# ESP32.net
KiCad netlist of a schematic drawn in Altium Designer
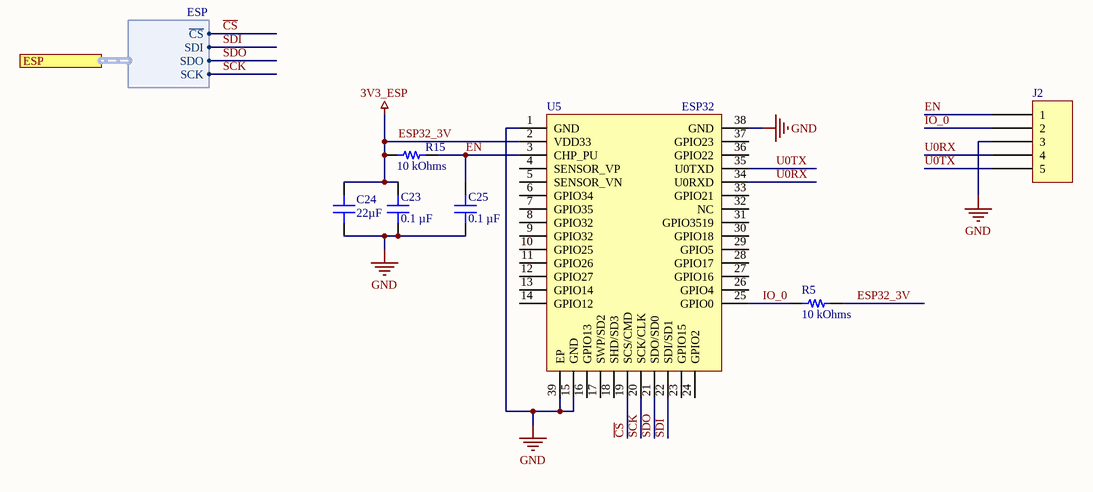
[diagram p0: ESP32.SchDoc]

(export (version "E")
  (design (tool "Eeschema 10.0.6"))
  (components
    (comp (ref "C23")
      (value "0.1 µF")
      (footprint "CAP 0402_1005")
      (description "CAP CER 0.1UF 25V X5R 0402")
      (fields
        (field (name "PART NUMBER") "C1005X5R1E104K050BC")
        (field (name "MANUFACTURER") "TDK Corporation")
      )
      (libsource (lib "Celestial Altium Library - altium_library") (part "Capacitor"))
    )
    (comp (ref "C24")
      (value "22µF")
      (footprint "CAP 0805_2012")
      (description "CAP CER 22UF 16V X5R 0805")
      (fields
        (field (name "PART NUMBER") "CL21A226MOQNNNE")
        (field (name "MANUFACTURER") "Samsung Electro-Mechanics")
      )
      (libsource (lib "Celestial Altium Library - altium_library") (part "Capacitor"))
    )
    (comp (ref "C25")
      (value "0.1 µF")
      (footprint "CAP 0402_1005")
      (description "CAP CER 0.1UF 25V X5R 0402")
      (fields
        (field (name "PART NUMBER") "C1005X5R1E104K050BC")
        (field (name "MANUFACTURER") "TDK Corporation")
      )
      (libsource (lib "Celestial Altium Library - altium_library") (part "Capacitor"))
    )
    (comp (ref "J2")
      (value "SM05B-SRSS-TB(LF)(SN)")
      (footprint "JST SM05B-SRSS-TB")
      (description "CONN HEADER SMD R/A 5POS 1MM")
      (fields (field (name "MANUFACTURER") "JST Sales America Inc."))
      (libsource (lib "Celestial Altium Library - altium_library") (part "5 Pin"))
    )
    (comp (ref "R5")
      (value "10 kOhms")
      (footprint "RES 0402_1005")
      (description "RES SMD 10K OHM 0.5% 1/16W 0402")
      (fields (field (name "PART NUMBER") "CRCW040210K0DHEDP") (field (name "MANUFACTURER") "Vishay Dale"))
      (libsource (lib "Celestial Altium Library - altium_library") (part "Resistor"))
    )
    (comp (ref "R15")
      (value "10 kOhms")
      (footprint "RES 0402_1005")
      (description "RES SMD 10K OHM 0.5% 1/16W 0402")
      (fields (field (name "PART NUMBER") "CRCW040210K0DHEDP") (field (name "MANUFACTURER") "Vishay Dale"))
      (libsource (lib "Celestial Altium Library - altium_library") (part "Resistor"))
    )
    (comp (ref "U5")
      (value "ESP32")
      (footprint "Espressif ESP32-WROOM-32")
      (libsource (lib "IC") (part "ESP32"))
    )
  )
  (nets
    (net (code "2") (name "/EN") (class "Default")
      (node (ref "C25") (pin "2") (pinfunction "2_2") (pintype "passive"))
      (node (ref "J2") (pin "1") (pinfunction "1_1") (pintype "passive"))
      (node (ref "R15") (pin "2") (pinfunction "2_2") (pintype "passive"))
      (node (ref "U5") (pin "3") (pinfunction "CHP_PU_3") (pintype "passive"))
    )
    (net (code "3") (name "/IO_0") (class "Default")
      (node (ref "J2") (pin "2") (pinfunction "2_2") (pintype "passive"))
      (node (ref "R5") (pin "1") (pinfunction "1_1") (pintype "passive"))
      (node (ref "U5") (pin "25") (pinfunction "GPIO0_25") (pintype "passive"))
    )
    (net (code "4") (name "/SCK") (class "Default")
      (node (ref "U5") (pin "20") (pinfunction "SCK/CLK_20") (pintype "passive"))
    )
    (net (code "5") (name "/SDI") (class "Default")
      (node (ref "U5") (pin "22") (pinfunction "SDI/SD1_22") (pintype "passive"))
    )
    (net (code "6") (name "/SDO") (class "Default")
      (node (ref "U5") (pin "21") (pinfunction "SDO/SD0_21") (pintype "passive"))
    )
    (net (code "7") (name "/U0RX") (class "Default")
      (node (ref "J2") (pin "4") (pinfunction "4_4") (pintype "passive"))
      (node (ref "U5") (pin "34") (pinfunction "U0RXD_34") (pintype "passive"))
    )
    (net (code "8") (name "/U0TX") (class "Default")
      (node (ref "J2") (pin "5") (pinfunction "5_5") (pintype "passive"))
      (node (ref "U5") (pin "35") (pinfunction "U0TXD_35") (pintype "passive"))
    )
    (net (code "10") (name "/~{CS}") (class "Default")
      (node (ref "U5") (pin "19") (pinfunction "SCS/CMD_19") (pintype "passive"))
    )
    (net (code "11") (name "3V3_ESP") (class "Default")
      (node (ref "C23") (pin "2") (pinfunction "2_2") (pintype "passive"))
      (node (ref "C24") (pin "2") (pinfunction "2_2") (pintype "passive"))
      (node (ref "R15") (pin "1") (pinfunction "1_1") (pintype "passive"))
      (node (ref "R5") (pin "2") (pinfunction "2_2") (pintype "passive"))
      (node (ref "U5") (pin "2") (pinfunction "VDD33_2") (pintype "passive"))
    )
    (net (code "12") (name "GND") (class "Default")
      (node (ref "C23") (pin "1") (pinfunction "1_1") (pintype "passive"))
      (node (ref "C24") (pin "1") (pinfunction "1_1") (pintype "passive"))
      (node (ref "C25") (pin "1") (pinfunction "1_1") (pintype "passive"))
      (node (ref "J2") (pin "3") (pinfunction "3_3") (pintype "passive"))
      (node (ref "U5") (pin "1") (pinfunction "GND_1") (pintype "passive"))
      (node (ref "U5") (pin "15") (pinfunction "GND_15") (pintype "passive"))
      (node (ref "U5") (pin "38") (pinfunction "GND_38") (pintype "passive"))
      (node (ref "U5") (pin "39") (pinfunction "EP_39") (pintype "passive"))
    )
    (net (code "13") (name "unconnected-(U5-GPIO2-Pad24)") (class "Default")
      (node (ref "U5") (pin "24") (pinfunction "GPIO2_24") (pintype "passive"))
    )
    (net (code "14") (name "unconnected-(U5-GPIO4-Pad26)") (class "Default")
      (node (ref "U5") (pin "26") (pinfunction "GPIO4_26") (pintype "passive"))
    )
    (net (code "15") (name "unconnected-(U5-GPIO5-Pad29)") (class "Default")
      (node (ref "U5") (pin "29") (pinfunction "GPIO5_29") (pintype "passive"))
    )
    (net (code "16") (name "unconnected-(U5-GPIO12-Pad14)") (class "Default")
      (node (ref "U5") (pin "14") (pinfunction "GPIO12_14") (pintype "passive"))
    )
    (net (code "17") (name "unconnected-(U5-GPIO13-Pad16)") (class "Default")
      (node (ref "U5") (pin "16") (pinfunction "GPIO13_16") (pintype "passive"))
    )
    (net (code "18") (name "unconnected-(U5-GPIO14-Pad13)") (class "Default")
      (node (ref "U5") (pin "13") (pinfunction "GPIO14_13") (pintype "passive"))
    )
    (net (code "19") (name "unconnected-(U5-GPIO15-Pad23)") (class "Default")
      (node (ref "U5") (pin "23") (pinfunction "GPIO15_23") (pintype "passive"))
    )
    (net (code "20") (name "unconnected-(U5-GPIO16-Pad27)") (class "Default")
      (node (ref "U5") (pin "27") (pinfunction "GPIO16_27") (pintype "passive"))
    )
    (net (code "21") (name "unconnected-(U5-GPIO17-Pad28)") (class "Default")
      (node (ref "U5") (pin "28") (pinfunction "GPIO17_28") (pintype "passive"))
    )
    (net (code "22") (name "unconnected-(U5-GPIO18-Pad30)") (class "Default")
      (node (ref "U5") (pin "30") (pinfunction "GPIO18_30") (pintype "passive"))
    )
    (net (code "23") (name "unconnected-(U5-GPIO21-Pad33)") (class "Default")
      (node (ref "U5") (pin "33") (pinfunction "GPIO21_33") (pintype "passive"))
    )
    (net (code "24") (name "unconnected-(U5-GPIO22-Pad36)") (class "Default")
      (node (ref "U5") (pin "36") (pinfunction "GPIO22_36") (pintype "passive"))
    )
    (net (code "25") (name "unconnected-(U5-GPIO23-Pad37)") (class "Default")
      (node (ref "U5") (pin "37") (pinfunction "GPIO23_37") (pintype "passive"))
    )
    (net (code "26") (name "unconnected-(U5-GPIO25-Pad10)") (class "Default")
      (node (ref "U5") (pin "10") (pinfunction "GPIO25_10") (pintype "passive"))
    )
    (net (code "27") (name "unconnected-(U5-GPIO26-Pad11)") (class "Default")
      (node (ref "U5") (pin "11") (pinfunction "GPIO26_11") (pintype "passive"))
    )
    (net (code "28") (name "unconnected-(U5-GPIO27-Pad12)") (class "Default")
      (node (ref "U5") (pin "12") (pinfunction "GPIO27_12") (pintype "passive"))
    )
    (net (code "29") (name "unconnected-(U5-GPIO32-Pad8)") (class "Default")
      (node (ref "U5") (pin "8") (pinfunction "GPIO32_8") (pintype "passive"))
    )
    (net (code "30") (name "unconnected-(U5-GPIO32-Pad9)") (class "Default")
      (node (ref "U5") (pin "9") (pinfunction "GPIO32_9") (pintype "passive"))
    )
    (net (code "31") (name "unconnected-(U5-GPIO34-Pad6)") (class "Default")
      (node (ref "U5") (pin "6") (pinfunction "GPIO34_6") (pintype "passive"))
    )
    (net (code "32") (name "unconnected-(U5-GPIO35-Pad7)") (class "Default")
      (node (ref "U5") (pin "7") (pinfunction "GPIO35_7") (pintype "passive"))
    )
    (net (code "33") (name "unconnected-(U5-GPIO3519-Pad31)") (class "Default")
      (node (ref "U5") (pin "31") (pinfunction "GPIO3519_31") (pintype "passive"))
    )
    (net (code "34") (name "unconnected-(U5-NC-Pad32)") (class "Default")
      (node (ref "U5") (pin "32") (pinfunction "NC_32") (pintype "passive"))
    )
    (net (code "35") (name "unconnected-(U5-SENSOR_VN-Pad5)") (class "Default")
      (node (ref "U5") (pin "5") (pinfunction "SENSOR_VN_5") (pintype "passive"))
    )
    (net (code "36") (name "unconnected-(U5-SENSOR_VP-Pad4)") (class "Default")
      (node (ref "U5") (pin "4") (pinfunction "SENSOR_VP_4") (pintype "passive"))
    )
    (net (code "37") (name "unconnected-(U5-SHD{slash}SD3-Pad18)") (class "Default")
      (node (ref "U5") (pin "18") (pinfunction "SHD/SD3_18") (pintype "passive"))
    )
    (net (code "38") (name "unconnected-(U5-SWP{slash}SD2-Pad17)") (class "Default")
      (node (ref "U5") (pin "17") (pinfunction "SWP/SD2_17") (pintype "passive"))
    )
  )
)
